# main.net
KiCad netlist of a schematic drawn in EAGLE
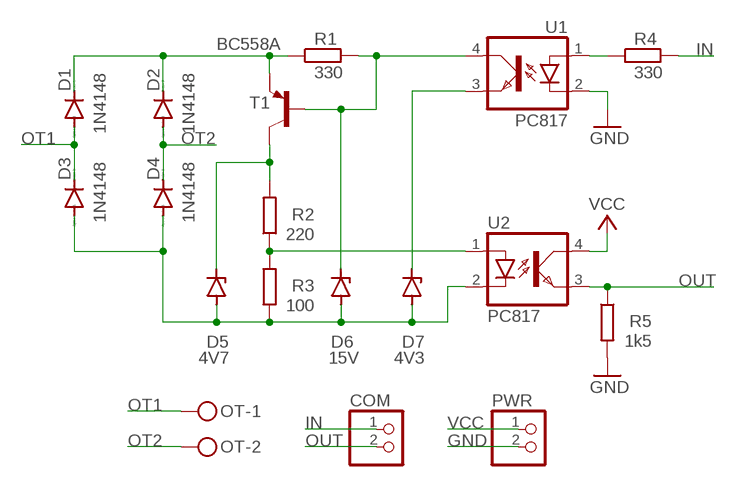
[diagram p0: schematic, sheet 1]

(export (version "E")
  (design (tool "Eeschema 10.0.6"))
  (components
    (comp (ref "COM")
      (value "PINHD-1X2")
      (footprint "eagle-import:1X02")
      (libsource (lib "eagle-import") (part "PINHD-1X2"))
    )
    (comp (ref "D1")
      (value "1N4148")
      (footprint "eagle-import:DO35-7")
      (libsource (lib "eagle-import") (part "1N4148DO35-7"))
    )
    (comp (ref "D2")
      (value "1N4148")
      (footprint "eagle-import:DO35-7")
      (libsource (lib "eagle-import") (part "1N4148DO35-7"))
    )
    (comp (ref "D3")
      (value "1N4148")
      (footprint "eagle-import:DO35-7")
      (libsource (lib "eagle-import") (part "1N4148DO35-7"))
    )
    (comp (ref "D4")
      (value "1N4148")
      (footprint "eagle-import:DO35-7")
      (libsource (lib "eagle-import") (part "1N4148DO35-7"))
    )
    (comp (ref "D5")
      (value "4V7")
      (footprint "eagle-import:ZDIO-7.5")
      (libsource (lib "eagle-import") (part "ZENER-DIODEZD-7.5"))
    )
    (comp (ref "D6")
      (value "15V")
      (footprint "eagle-import:ZDIO-7.5")
      (libsource (lib "eagle-import") (part "ZENER-DIODEZD-7.5"))
    )
    (comp (ref "D7")
      (value "4V3")
      (footprint "eagle-import:ZDIO-7.5")
      (libsource (lib "eagle-import") (part "ZENER-DIODEZD-7.5"))
    )
    (comp (ref "OT")
      (value "MKDSN1,5/2-5,08")
      (footprint "eagle-import:MKDSN1,5_2-5,08")
      (libsource (lib "eagle-import") (part "MKDSN1,5/2-5,08"))
    )
    (comp (ref "PWR")
      (value "PINHD-1X2")
      (footprint "eagle-import:1X02")
      (libsource (lib "eagle-import") (part "PINHD-1X2"))
    )
    (comp (ref "R1")
      (value "330")
      (footprint "eagle-import:0207_10")
      (libsource (lib "eagle-import") (part "R-EU_0207/10"))
    )
    (comp (ref "R2")
      (value "220")
      (footprint "eagle-import:0207_10")
      (libsource (lib "eagle-import") (part "R-EU_0207/10"))
    )
    (comp (ref "R3")
      (value "100")
      (footprint "eagle-import:0207_10")
      (libsource (lib "eagle-import") (part "R-EU_0207/10"))
    )
    (comp (ref "R4")
      (value "330")
      (footprint "eagle-import:0207_10")
      (libsource (lib "eagle-import") (part "R-EU_0207/10"))
    )
    (comp (ref "R5")
      (value "1k5")
      (footprint "eagle-import:0207_10")
      (libsource (lib "eagle-import") (part "R-EU_0207/10"))
    )
    (comp (ref "T1")
      (value "BC558A")
      (footprint "eagle-import:TO92-EBC")
      (libsource (lib "eagle-import") (part "-PNP-TO92-EBCBC558A"))
    )
    (comp (ref "U1")
      (value "PC817")
      (footprint "eagle-import:DIL04")
      (fields (field (name "MPN") "PC817X4J000F"))
      (libsource (lib "eagle-import") (part "PC817"))
    )
    (comp (ref "U2")
      (value "PC817")
      (footprint "eagle-import:DIL04")
      (fields (field (name "MPN") "PC817X4J000F"))
      (libsource (lib "eagle-import") (part "PC817"))
    )
  )
  (nets
    (net (code "1") (name "/IN") (class "Default")
      (node (ref "COM") (pin "1") (pinfunction "1_1") (pintype "passive"))
      (node (ref "R4") (pin "2") (pinfunction "2_2") (pintype "passive"))
    )
    (net (code "2") (name "/OT1") (class "Default")
      (node (ref "D1") (pin "A") (pinfunction "A_A") (pintype "passive"))
      (node (ref "D3") (pin "C") (pinfunction "C_C") (pintype "passive"))
      (node (ref "OT") (pin "1") (pinfunction "KL_1") (pintype "passive"))
    )
    (net (code "3") (name "/OT2") (class "Default")
      (node (ref "D2") (pin "A") (pinfunction "A_A") (pintype "passive"))
      (node (ref "D4") (pin "C") (pinfunction "C_C") (pintype "passive"))
      (node (ref "OT") (pin "2") (pinfunction "KL_2") (pintype "passive"))
    )
    (net (code "4") (name "/OUT") (class "Default")
      (node (ref "COM") (pin "2") (pinfunction "2_2") (pintype "passive"))
      (node (ref "R5") (pin "1") (pinfunction "1_1") (pintype "passive"))
      (node (ref "U2") (pin "3") (pinfunction "EMIT_3") (pintype "passive"))
    )
    (net (code "5") (name "GND") (class "Default")
      (node (ref "PWR") (pin "2") (pinfunction "2_2") (pintype "passive"))
      (node (ref "R5") (pin "2") (pinfunction "2_2") (pintype "passive"))
      (node (ref "U1") (pin "2") (pinfunction "C_2") (pintype "passive"))
    )
    (net (code "6") (name "Net-(D1-PadC)") (class "Default")
      (node (ref "D1") (pin "C") (pinfunction "C_C") (pintype "passive"))
      (node (ref "D2") (pin "C") (pinfunction "C_C") (pintype "passive"))
      (node (ref "R1") (pin "1") (pinfunction "1_1") (pintype "passive"))
      (node (ref "T1") (pin "E") (pinfunction "E_E") (pintype "passive"))
    )
    (net (code "7") (name "Net-(D5-PadC)") (class "Default")
      (node (ref "D5") (pin "C") (pinfunction "C_C") (pintype "passive"))
      (node (ref "R2") (pin "2") (pinfunction "2_2") (pintype "passive"))
      (node (ref "T1") (pin "C") (pinfunction "C_C") (pintype "passive"))
    )
    (net (code "8") (name "Net-(U1-A)") (class "Default")
      (node (ref "R4") (pin "1") (pinfunction "1_1") (pintype "passive"))
      (node (ref "U1") (pin "1") (pinfunction "A_1") (pintype "passive"))
    )
    (net (code "9") (name "Net-(U1-COL)") (class "Default")
      (node (ref "D6") (pin "C") (pinfunction "C_C") (pintype "passive"))
      (node (ref "R1") (pin "2") (pinfunction "2_2") (pintype "passive"))
      (node (ref "T1") (pin "B") (pinfunction "B_B") (pintype "passive"))
      (node (ref "U1") (pin "4") (pinfunction "COL_4") (pintype "passive"))
    )
    (net (code "10") (name "Net-(U1-EMIT)") (class "Default")
      (node (ref "D7") (pin "C") (pinfunction "C_C") (pintype "passive"))
      (node (ref "U1") (pin "3") (pinfunction "EMIT_3") (pintype "passive"))
    )
    (net (code "11") (name "Net-(U2-A)") (class "Default")
      (node (ref "R2") (pin "1") (pinfunction "1_1") (pintype "passive"))
      (node (ref "R3") (pin "2") (pinfunction "2_2") (pintype "passive"))
      (node (ref "U2") (pin "1") (pinfunction "A_1") (pintype "passive"))
    )
    (net (code "12") (name "Net-(U2-C)") (class "Default")
      (node (ref "D3") (pin "A") (pinfunction "A_A") (pintype "passive"))
      (node (ref "D4") (pin "A") (pinfunction "A_A") (pintype "passive"))
      (node (ref "D5") (pin "A") (pinfunction "A_A") (pintype "passive"))
      (node (ref "D6") (pin "A") (pinfunction "A_A") (pintype "passive"))
      (node (ref "D7") (pin "A") (pinfunction "A_A") (pintype "passive"))
      (node (ref "R3") (pin "1") (pinfunction "1_1") (pintype "passive"))
      (node (ref "U2") (pin "2") (pinfunction "C_2") (pintype "passive"))
    )
    (net (code "13") (name "VCC") (class "Default")
      (node (ref "PWR") (pin "1") (pinfunction "1_1") (pintype "passive"))
      (node (ref "U2") (pin "4") (pinfunction "COL_4") (pintype "passive"))
    )
  )
)
